# LoraPic.net
KiCad netlist of a schematic drawn in Altium Designer
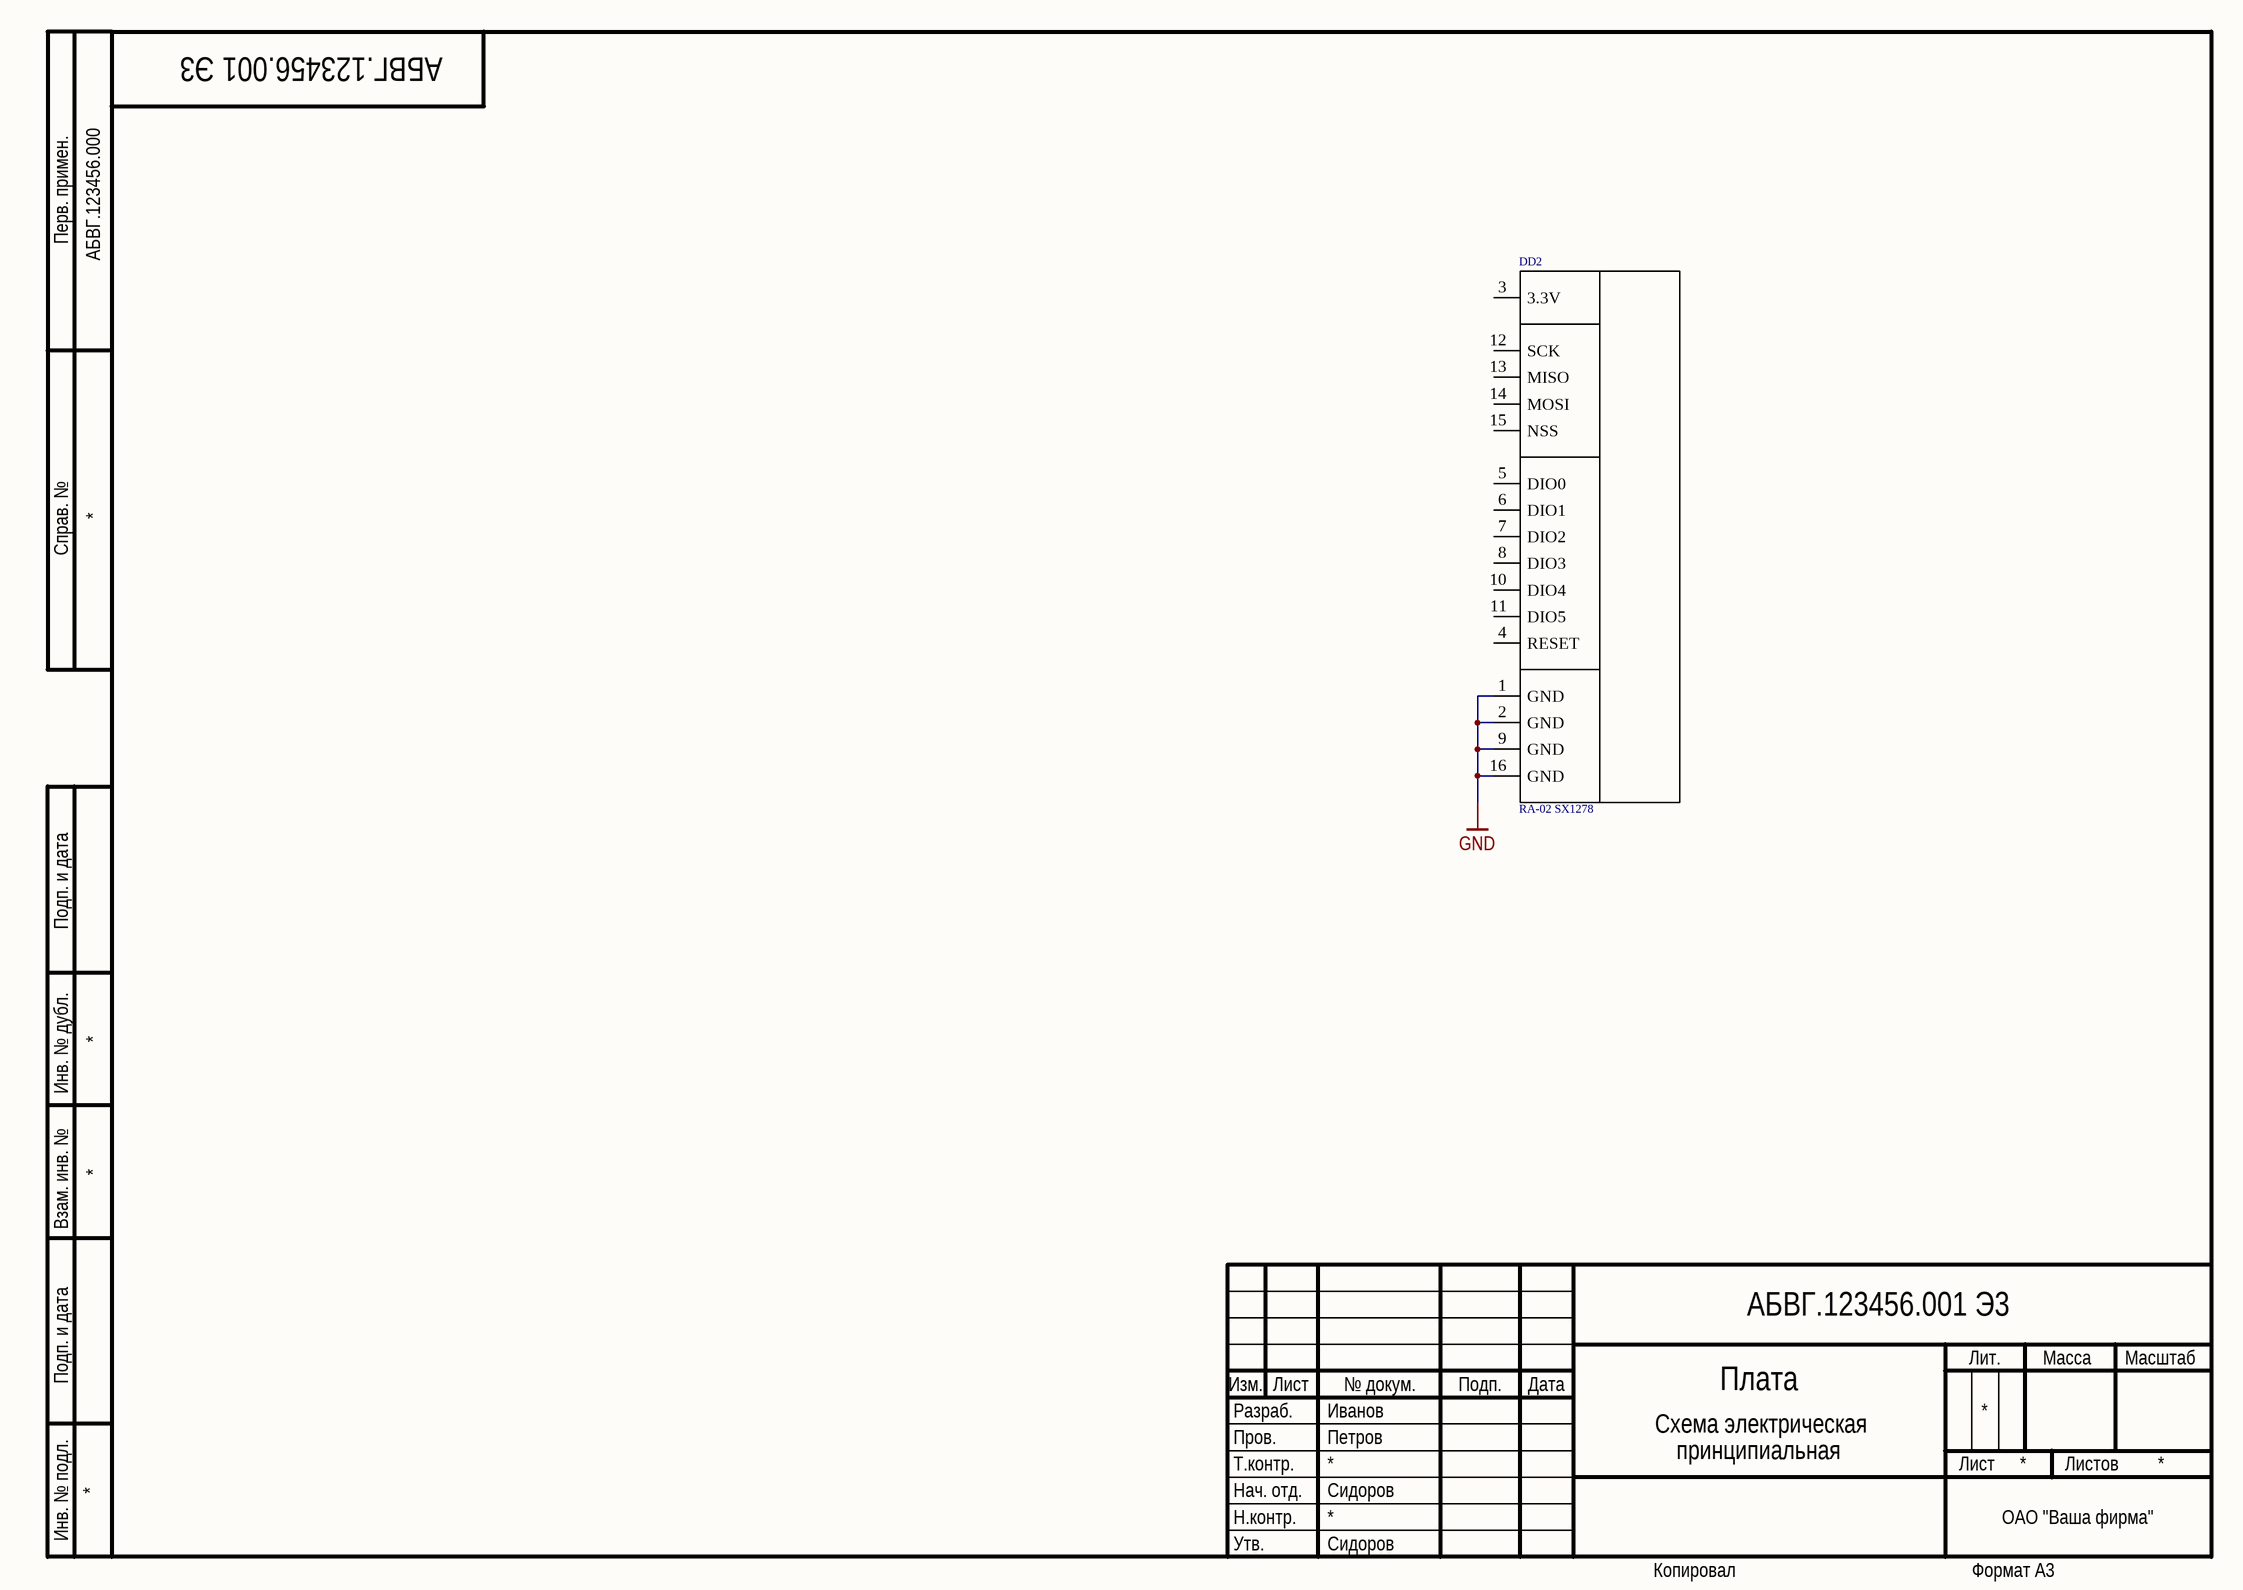
[diagram p0: LoraPic.SchDoc]

(export (version "E")
  (design (tool "Eeschema 10.0.6"))
  (components
    (comp (ref "DD2") (value "RA-02 SX1278") (footprint "RA-02") (libsource (lib "RA-02") (part "RA-02")))
  )
  (nets
    (net (code "1") (name "GND") (class "Default")
      (node (ref "DD2") (pin "1") (pinfunction "GND_1") (pintype "passive"))
      (node (ref "DD2") (pin "16") (pinfunction "GND_16") (pintype "passive"))
      (node (ref "DD2") (pin "2") (pinfunction "GND_2") (pintype "passive"))
      (node (ref "DD2") (pin "9") (pinfunction "GND_9") (pintype "passive"))
    )
    (net (code "2") (name "unconnected-(DD2-3.3V-Pad3)") (class "Default")
      (node (ref "DD2") (pin "3") (pinfunction "3.3V_3") (pintype "passive"))
    )
    (net (code "3") (name "unconnected-(DD2-DIO0-Pad5)") (class "Default")
      (node (ref "DD2") (pin "5") (pinfunction "DIO0_5") (pintype "passive"))
    )
    (net (code "4") (name "unconnected-(DD2-DIO1-Pad6)") (class "Default")
      (node (ref "DD2") (pin "6") (pinfunction "DIO1_6") (pintype "passive"))
    )
    (net (code "5") (name "unconnected-(DD2-DIO2-Pad7)") (class "Default")
      (node (ref "DD2") (pin "7") (pinfunction "DIO2_7") (pintype "passive"))
    )
    (net (code "6") (name "unconnected-(DD2-DIO3-Pad8)") (class "Default")
      (node (ref "DD2") (pin "8") (pinfunction "DIO3_8") (pintype "passive"))
    )
    (net (code "7") (name "unconnected-(DD2-DIO4-Pad10)") (class "Default")
      (node (ref "DD2") (pin "10") (pinfunction "DIO4_10") (pintype "passive"))
    )
    (net (code "8") (name "unconnected-(DD2-DIO5-Pad11)") (class "Default")
      (node (ref "DD2") (pin "11") (pinfunction "DIO5_11") (pintype "passive"))
    )
    (net (code "9") (name "unconnected-(DD2-MISO-Pad13)") (class "Default")
      (node (ref "DD2") (pin "13") (pinfunction "MISO_13") (pintype "passive"))
    )
    (net (code "10") (name "unconnected-(DD2-MOSI-Pad14)") (class "Default")
      (node (ref "DD2") (pin "14") (pinfunction "MOSI_14") (pintype "passive"))
    )
    (net (code "11") (name "unconnected-(DD2-NSS-Pad15)") (class "Default")
      (node (ref "DD2") (pin "15") (pinfunction "NSS_15") (pintype "passive"))
    )
    (net (code "12") (name "unconnected-(DD2-RESET-Pad4)") (class "Default")
      (node (ref "DD2") (pin "4") (pinfunction "RESET_4") (pintype "passive"))
    )
    (net (code "13") (name "unconnected-(DD2-SCK-Pad12)") (class "Default")
      (node (ref "DD2") (pin "12") (pinfunction "SCK_12") (pintype "passive"))
    )
  )
)
